# Sheet1.net
KiCad netlist of a schematic drawn in Altium Designer
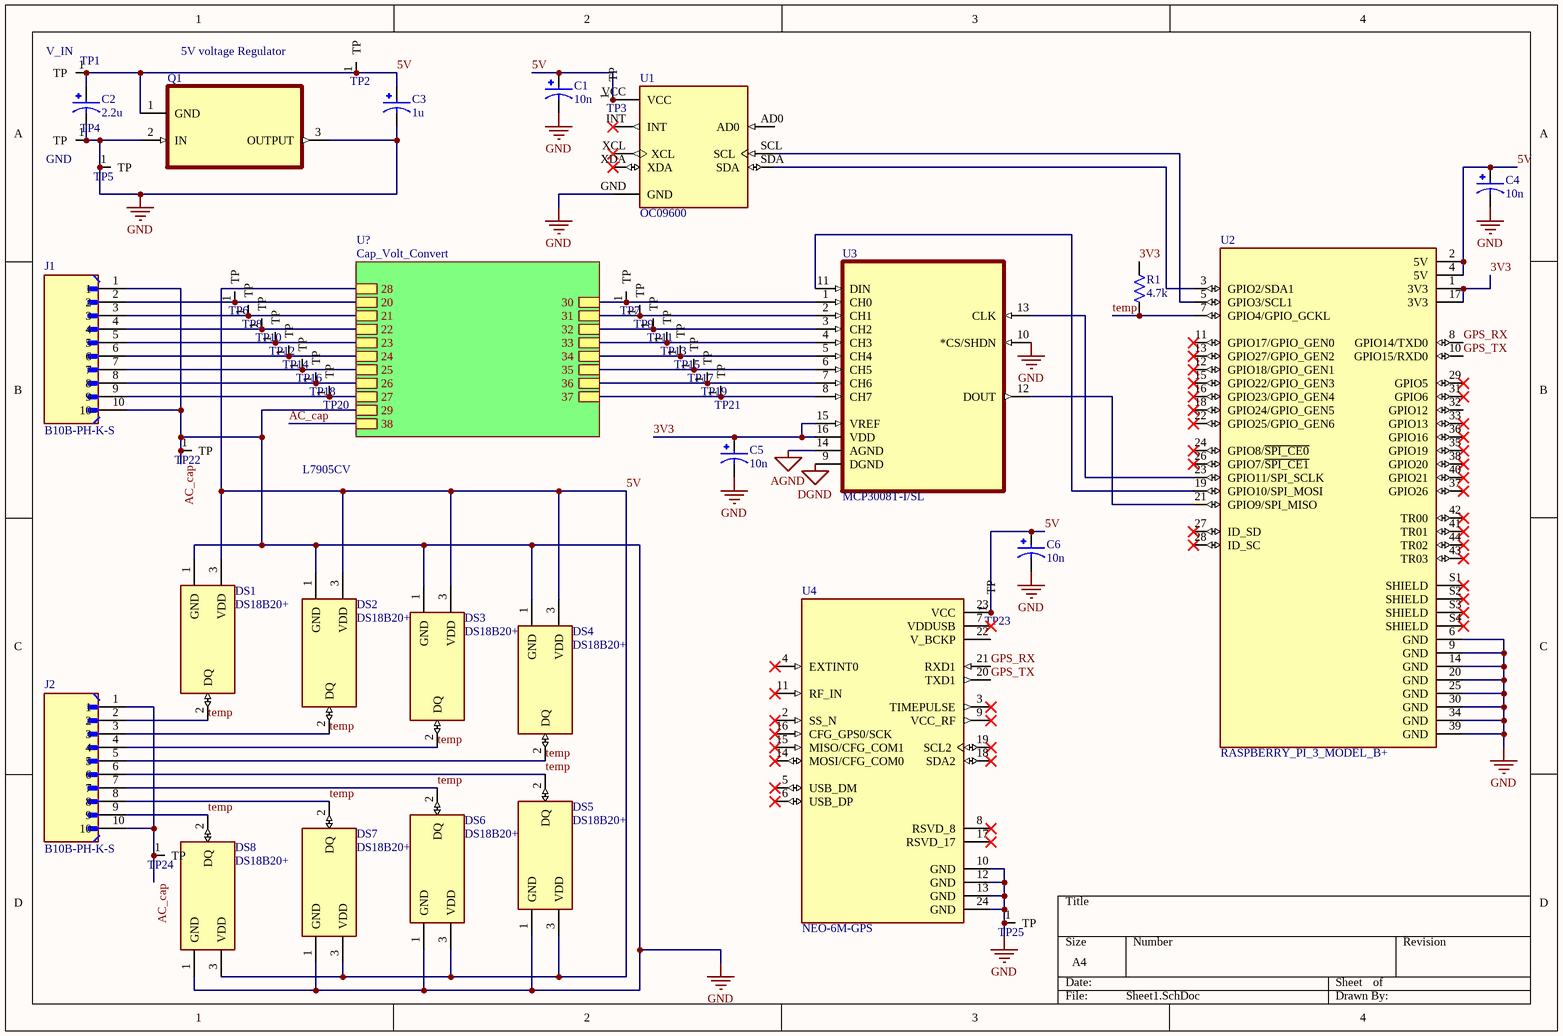
[diagram p0: Sheet1.SchDoc]

(export (version "E")
  (design (tool "Eeschema 10.0.6"))
  (components
    (comp (ref "C1")
      (value "10n")
      (footprint "CAPPRD750W80D1600H2000")
      (description "CAP ALUM 680UF 20% 63V THRU HOLE")
      (fields (field (name "MP") "EEU-FS1J681S") (field (name "MF") "Panasonic Electronic Components"))
      (libsource (lib "Schlib1") (part "EEUFS1J681S"))
    )
    (comp (ref "C2")
      (value "2.2u")
      (footprint "CAPPRD750W80D1600H2000")
      (description "CAP ALUM 680UF 20% 63V THRU HOLE")
      (fields (field (name "MP") "EEU-FS1J681S") (field (name "MF") "Panasonic Electronic Components"))
      (libsource (lib "Schlib1") (part "EEUFS1J681S"))
    )
    (comp (ref "C3")
      (value "1u")
      (footprint "CAPPRD750W80D1600H2000")
      (description "CAP ALUM 680UF 20% 63V THRU HOLE")
      (fields (field (name "MP") "EEU-FS1J681S") (field (name "MF") "Panasonic Electronic Components"))
      (libsource (lib "Schlib1") (part "EEUFS1J681S"))
    )
    (comp (ref "C4")
      (value "10n")
      (footprint "CAPPRD750W80D1600H2000")
      (description "CAP ALUM 680UF 20% 63V THRU HOLE")
      (fields (field (name "MP") "EEU-FS1J681S") (field (name "MF") "Panasonic Electronic Components"))
      (libsource (lib "Schlib1") (part "EEUFS1J681S"))
    )
    (comp (ref "C5")
      (value "10n")
      (footprint "CAPPRD750W80D1600H2000")
      (description "CAP ALUM 680UF 20% 63V THRU HOLE")
      (fields (field (name "MP") "EEU-FS1J681S") (field (name "MF") "Panasonic Electronic Components"))
      (libsource (lib "Schlib1") (part "EEUFS1J681S"))
    )
    (comp (ref "C6")
      (value "10n")
      (footprint "CAPPRD750W80D1600H2000")
      (description "CAP ALUM 680UF 20% 63V THRU HOLE")
      (fields (field (name "MP") "EEU-FS1J681S") (field (name "MF") "Panasonic Electronic Components"))
      (libsource (lib "Schlib1") (part "EEUFS1J681S"))
    )
    (comp (ref "DS1")
      (value "DS18B20+")
      (footprint "IC_DS18B20+")
      (description "Programmable Resolution 1-Wire Digital Thermometer")
      (fields (field (name "MF") "Analog Devices"))
      (libsource (lib "") (part "DS18B20+_1"))
    )
    (comp (ref "DS2")
      (value "DS18B20+")
      (footprint "IC_DS18B20+")
      (description "Programmable Resolution 1-Wire Digital Thermometer")
      (fields (field (name "MF") "Analog Devices"))
      (libsource (lib "") (part "DS18B20+_1"))
    )
    (comp (ref "DS3")
      (value "DS18B20+")
      (footprint "IC_DS18B20+")
      (description "Programmable Resolution 1-Wire Digital Thermometer")
      (fields (field (name "MF") "Analog Devices"))
      (libsource (lib "") (part "DS18B20+_1"))
    )
    (comp (ref "DS4")
      (value "DS18B20+")
      (footprint "IC_DS18B20+")
      (description "Programmable Resolution 1-Wire Digital Thermometer")
      (fields (field (name "MF") "Analog Devices"))
      (libsource (lib "") (part "DS18B20+_1"))
    )
    (comp (ref "DS5")
      (value "DS18B20+")
      (footprint "IC_DS18B20+")
      (description "Programmable Resolution 1-Wire Digital Thermometer")
      (fields (field (name "MF") "Analog Devices"))
      (libsource (lib "Schlib1") (part "DS18B20+"))
    )
    (comp (ref "DS6")
      (value "DS18B20+")
      (footprint "IC_DS18B20+")
      (description "Programmable Resolution 1-Wire Digital Thermometer")
      (fields (field (name "MF") "Analog Devices"))
      (libsource (lib "Schlib1") (part "DS18B20+"))
    )
    (comp (ref "DS7")
      (value "DS18B20+")
      (footprint "IC_DS18B20+")
      (description "Programmable Resolution 1-Wire Digital Thermometer")
      (fields (field (name "MF") "Analog Devices"))
      (libsource (lib "Schlib1") (part "DS18B20+"))
    )
    (comp (ref "DS8")
      (value "DS18B20+")
      (footprint "IC_DS18B20+")
      (description "Programmable Resolution 1-Wire Digital Thermometer")
      (fields (field (name "MF") "Analog Devices"))
      (libsource (lib "Schlib1") (part "DS18B20+"))
    )
    (comp (ref "J1")
      (value "B10B-PH-K-S")
      (footprint "JST_B10B-PH-K-S")
      (description "2.0 mm pitch/Disconnectable Crimp style connectors")
      (fields (field (name "MF") "JST Sales America Inc."))
      (libsource (lib "Schlib1") (part "B10B-PH-K-S"))
    )
    (comp (ref "J2")
      (value "B10B-PH-K-S")
      (footprint "JST_B10B-PH-K-S")
      (description "2.0 mm pitch/Disconnectable Crimp style connectors")
      (fields (field (name "MF") "JST Sales America Inc."))
      (libsource (lib "Schlib1") (part "B10B-PH-K-S"))
    )
    (comp (ref "Q1")
      (value "L7905CV")
      (footprint "TO254P450X1020X1935-3P")
      (description "Linear Voltage Regulator IC Negative Fixed 1 Output 1.5A TO-220")
      (fields (field (name "MF") "STMicroelectronics"))
      (libsource (lib "Schlib1") (part "L7905CV"))
    )
    (comp (ref "R1")
      (value "4.7k")
      (footprint "RESAD730W45L370D210")
      (description "Metal Film Resistors - Through Hole")
      (fields (field (name "MF") "YAGEO") (field (name "MP") "MFR-12FTE52-12K5"))
      (libsource (lib "Schlib1") (part "MFR-12FTE52-12K5"))
    )
    (comp (ref "TP1") (value "V_IN") (footprint "Testpoint") (libsource (lib "Schlib1") (part "Testpoint")))
    (comp (ref "TP2")
      (value "Testpoint")
      (footprint "Testpoint SMD")
      (libsource (lib "Schlib1") (part "Testpoint"))
    )
    (comp (ref "TP3")
      (value "Testpoint")
      (footprint "Testpoint SMD")
      (libsource (lib "Schlib1") (part "Testpoint"))
    )
    (comp (ref "TP4") (value "GND") (footprint "Testpoint") (libsource (lib "Schlib1") (part "Testpoint")))
    (comp (ref "TP5")
      (value "Testpoint")
      (footprint "Testpoint SMD")
      (libsource (lib "Schlib1") (part "Testpoint"))
    )
    (comp (ref "TP6")
      (value "Testpoint")
      (footprint "Testpoint SMD")
      (libsource (lib "Schlib1") (part "Testpoint"))
    )
    (comp (ref "TP7")
      (value "Testpoint")
      (footprint "Testpoint SMD")
      (libsource (lib "Schlib1") (part "Testpoint"))
    )
    (comp (ref "TP8")
      (value "Testpoint")
      (footprint "Testpoint SMD")
      (libsource (lib "Schlib1") (part "Testpoint"))
    )
    (comp (ref "TP9")
      (value "Testpoint")
      (footprint "Testpoint SMD")
      (libsource (lib "Schlib1") (part "Testpoint"))
    )
    (comp (ref "TP10")
      (value "Testpoint")
      (footprint "Testpoint SMD")
      (libsource (lib "Schlib1") (part "Testpoint"))
    )
    (comp (ref "TP11")
      (value "Testpoint")
      (footprint "Testpoint SMD")
      (libsource (lib "Schlib1") (part "Testpoint"))
    )
    (comp (ref "TP12")
      (value "Testpoint")
      (footprint "Testpoint SMD")
      (libsource (lib "Schlib1") (part "Testpoint"))
    )
    (comp (ref "TP13")
      (value "Testpoint")
      (footprint "Testpoint SMD")
      (libsource (lib "Schlib1") (part "Testpoint"))
    )
    (comp (ref "TP14")
      (value "Testpoint")
      (footprint "Testpoint SMD")
      (libsource (lib "Schlib1") (part "Testpoint"))
    )
    (comp (ref "TP15")
      (value "Testpoint")
      (footprint "Testpoint SMD")
      (libsource (lib "Schlib1") (part "Testpoint"))
    )
    (comp (ref "TP16")
      (value "Testpoint")
      (footprint "Testpoint SMD")
      (libsource (lib "Schlib1") (part "Testpoint"))
    )
    (comp (ref "TP17")
      (value "Testpoint")
      (footprint "Testpoint SMD")
      (libsource (lib "Schlib1") (part "Testpoint"))
    )
    (comp (ref "TP18")
      (value "Testpoint")
      (footprint "Testpoint SMD")
      (libsource (lib "Schlib1") (part "Testpoint"))
    )
    (comp (ref "TP19")
      (value "Testpoint")
      (footprint "Testpoint SMD")
      (libsource (lib "Schlib1") (part "Testpoint"))
    )
    (comp (ref "TP20")
      (value "Testpoint")
      (footprint "Testpoint SMD")
      (libsource (lib "Schlib1") (part "Testpoint"))
    )
    (comp (ref "TP21")
      (value "Testpoint")
      (footprint "Testpoint SMD")
      (libsource (lib "Schlib1") (part "Testpoint"))
    )
    (comp (ref "TP22")
      (value "Testpoint")
      (footprint "Testpoint")
      (libsource (lib "Schlib1") (part "Testpoint"))
    )
    (comp (ref "TP23")
      (value "Testpoint")
      (footprint "Testpoint SMD")
      (libsource (lib "Schlib1") (part "Testpoint"))
    )
    (comp (ref "TP24")
      (value "Testpoint")
      (footprint "Testpoint SMD")
      (libsource (lib "Schlib1") (part "Testpoint"))
    )
    (comp (ref "TP25")
      (value "Testpoint")
      (footprint "Testpoint SMD")
      (libsource (lib "Schlib1") (part "Testpoint"))
    )
    (comp (ref "U1")
      (value "OC09600")
      (footprint "MODULE_OC09600")
      (description "GY-521 6 DOF MPU-6050 Module 3 Axis Accelerometer Gyroscope Module for Arduino")
      (fields (field (name "MF") "YKS"))
      (libsource (lib "Schlib1") (part "OC09600"))
    )
    (comp (ref "U2")
      (value "RASPBERRY_PI_3_MODEL_B+")
      (footprint "MODULE_RASPBERRY_PI_3_MODEL_B+")
      (fields (field (name "MF") "Raspberry Pi") (field (name "MP") "RASPBERRY PI 3 MODEL B+"))
      (libsource (lib "Schlib1") (part "RASPBERRY_PI_3_MODEL_B+"))
    )
    (comp (ref "U3")
      (value "MCP3008T-I/SL")
      (footprint "SOIC127P600X175-16N")
      (description "10-bit ADC, SPI, 8-channel16 SOIC .150in T/R ¦ Microchip Technology Inc. MCP3008T-I/SL")
      (fields (field (name "MF") "Microchip Technology"))
      (libsource (lib "Schlib1") (part "MCP3008T-I/SL"))
    )
    (comp (ref "U4")
      (value "NEO-6M-GPS")
      (footprint "XCVR_NEO-6M-GPS")
      (description "GPS Development Tools SparkFun GNSS-RTK Dead Reckoning Breakout - ZED-F9K (Qwiic)")
      (fields (field (name "MF") "u-blox"))
      (libsource (lib "Schlib1") (part "NEO-6M-GPS"))
    )
  )
  (nets
    (net (code "1") (name "/3V3") (class "Default")
      (node (ref "C5") (pin "P") (pinfunction "P_P") (pintype "passive"))
      (node (ref "R1") (pin "2") (pinfunction "2_2") (pintype "passive"))
      (node (ref "U2") (pin "1") (pinfunction "3V3_1") (pintype "power_in"))
      (node (ref "U2") (pin "17") (pinfunction "3V3_17") (pintype "power_in"))
      (node (ref "U3") (pin "15") (pinfunction "VREF_15") (pintype "input"))
      (node (ref "U3") (pin "16") (pinfunction "VDD_16") (pintype "power_in"))
    )
    (net (code "2") (name "/5V") (class "Default")
      (node (ref "C1") (pin "P") (pinfunction "P_P") (pintype "passive"))
      (node (ref "C2") (pin "P") (pinfunction "P_P") (pintype "passive"))
      (node (ref "C3") (pin "P") (pinfunction "P_P") (pintype "passive"))
      (node (ref "C4") (pin "P") (pinfunction "P_P") (pintype "passive"))
      (node (ref "C6") (pin "P") (pinfunction "P_P") (pintype "passive"))
      (node (ref "DS1") (pin "3") (pinfunction "VDD_3") (pintype "power_in"))
      (node (ref "DS2") (pin "3") (pinfunction "VDD_3") (pintype "power_in"))
      (node (ref "DS3") (pin "3") (pinfunction "VDD_3") (pintype "power_in"))
      (node (ref "DS4") (pin "3") (pinfunction "VDD_3") (pintype "power_in"))
      (node (ref "DS5") (pin "3") (pinfunction "VDD_3") (pintype "power_in"))
      (node (ref "DS6") (pin "3") (pinfunction "VDD_3") (pintype "power_in"))
      (node (ref "DS7") (pin "3") (pinfunction "VDD_3") (pintype "power_in"))
      (node (ref "DS8") (pin "3") (pinfunction "VDD_3") (pintype "power_in"))
      (node (ref "Q1") (pin "1") (pinfunction "GND_1") (pintype "passive"))
      (node (ref "TP1") (pin "1") (pinfunction "TP_1") (pintype "passive"))
      (node (ref "TP2") (pin "1") (pinfunction "TP_1") (pintype "passive"))
      (node (ref "TP23") (pin "1") (pinfunction "TP_1") (pintype "passive"))
      (node (ref "TP3") (pin "1") (pinfunction "TP_1") (pintype "passive"))
      (node (ref "U1") (pin "VCC") (pinfunction "VCC_VCC") (pintype "power_in"))
      (node (ref "U2") (pin "2") (pinfunction "5V_2") (pintype "power_in"))
      (node (ref "U2") (pin "4") (pinfunction "5V_4") (pintype "power_in"))
      (node (ref "U4") (pin "23") (pinfunction "VCC_23") (pintype "power_in"))
    )
    (net (code "3") (name "/20") (class "Default")
      (node (ref "J1") (pin "2") (pinfunction "2_2") (pintype "passive"))
      (node (ref "TP6") (pin "1") (pinfunction "TP_1") (pintype "passive"))
    )
    (net (code "4") (name "/21") (class "Default")
      (node (ref "J1") (pin "3") (pinfunction "3_3") (pintype "passive"))
      (node (ref "TP8") (pin "1") (pinfunction "TP_1") (pintype "passive"))
    )
    (net (code "5") (name "/22") (class "Default")
      (node (ref "J1") (pin "4") (pinfunction "4_4") (pintype "passive"))
      (node (ref "TP10") (pin "1") (pinfunction "TP_1") (pintype "passive"))
    )
    (net (code "6") (name "/23") (class "Default")
      (node (ref "J1") (pin "5") (pinfunction "5_5") (pintype "passive"))
      (node (ref "TP12") (pin "1") (pinfunction "TP_1") (pintype "passive"))
    )
    (net (code "7") (name "/24") (class "Default")
      (node (ref "J1") (pin "6") (pinfunction "6_6") (pintype "passive"))
      (node (ref "TP14") (pin "1") (pinfunction "TP_1") (pintype "passive"))
    )
    (net (code "8") (name "/25") (class "Default")
      (node (ref "J1") (pin "7") (pinfunction "7_7") (pintype "passive"))
      (node (ref "TP16") (pin "1") (pinfunction "TP_1") (pintype "passive"))
    )
    (net (code "9") (name "/26") (class "Default")
      (node (ref "J1") (pin "8") (pinfunction "8_8") (pintype "passive"))
      (node (ref "TP18") (pin "1") (pinfunction "TP_1") (pintype "passive"))
    )
    (net (code "10") (name "/27") (class "Default")
      (node (ref "J1") (pin "9") (pinfunction "9_9") (pintype "passive"))
      (node (ref "TP20") (pin "1") (pinfunction "TP_1") (pintype "passive"))
    )
    (net (code "11") (name "/30") (class "Default")
      (node (ref "TP7") (pin "1") (pinfunction "TP_1") (pintype "passive"))
      (node (ref "U3") (pin "1") (pinfunction "CH0_1") (pintype "input"))
    )
    (net (code "12") (name "/31") (class "Default")
      (node (ref "TP9") (pin "1") (pinfunction "TP_1") (pintype "passive"))
      (node (ref "U3") (pin "2") (pinfunction "CH1_2") (pintype "input"))
    )
    (net (code "13") (name "/32") (class "Default")
      (node (ref "TP11") (pin "1") (pinfunction "TP_1") (pintype "passive"))
      (node (ref "U3") (pin "3") (pinfunction "CH2_3") (pintype "input"))
    )
    (net (code "14") (name "/33") (class "Default")
      (node (ref "TP13") (pin "1") (pinfunction "TP_1") (pintype "passive"))
      (node (ref "U3") (pin "4") (pinfunction "CH3_4") (pintype "input"))
    )
    (net (code "15") (name "/34") (class "Default")
      (node (ref "TP15") (pin "1") (pinfunction "TP_1") (pintype "passive"))
      (node (ref "U3") (pin "5") (pinfunction "CH4_5") (pintype "input"))
    )
    (net (code "16") (name "/35") (class "Default")
      (node (ref "TP17") (pin "1") (pinfunction "TP_1") (pintype "passive"))
      (node (ref "U3") (pin "6") (pinfunction "CH5_6") (pintype "input"))
    )
    (net (code "17") (name "/36") (class "Default")
      (node (ref "TP19") (pin "1") (pinfunction "TP_1") (pintype "passive"))
      (node (ref "U3") (pin "7") (pinfunction "CH6_7") (pintype "input"))
    )
    (net (code "18") (name "/37") (class "Default")
      (node (ref "TP21") (pin "1") (pinfunction "TP_1") (pintype "passive"))
      (node (ref "U3") (pin "8") (pinfunction "CH7_8") (pintype "input"))
    )
    (net (code "19") (name "/GPS_RX") (class "Default")
      (node (ref "U2") (pin "8") (pinfunction "GPIO14/TXD0_8") (pintype "bidirectional"))
      (node (ref "U4") (pin "21") (pinfunction "RXD1_21") (pintype "input"))
    )
    (net (code "20") (name "/GPS_TX") (class "Default")
      (node (ref "U2") (pin "10") (pinfunction "GPIO15/RXD0_10") (pintype "bidirectional"))
      (node (ref "U4") (pin "20") (pinfunction "TXD1_20") (pintype "output"))
    )
    (net (code "21") (name "/temp") (class "Default")
      (node (ref "DS1") (pin "2") (pinfunction "DQ_2") (pintype "bidirectional"))
      (node (ref "DS2") (pin "2") (pinfunction "DQ_2") (pintype "bidirectional"))
      (node (ref "DS3") (pin "2") (pinfunction "DQ_2") (pintype "bidirectional"))
      (node (ref "DS4") (pin "2") (pinfunction "DQ_2") (pintype "bidirectional"))
      (node (ref "DS5") (pin "2") (pinfunction "DQ_2") (pintype "bidirectional"))
      (node (ref "DS6") (pin "2") (pinfunction "DQ_2") (pintype "bidirectional"))
      (node (ref "DS7") (pin "2") (pinfunction "DQ_2") (pintype "bidirectional"))
      (node (ref "DS8") (pin "2") (pinfunction "DQ_2") (pintype "bidirectional"))
      (node (ref "J2") (pin "2") (pinfunction "2_2") (pintype "passive"))
      (node (ref "J2") (pin "3") (pinfunction "3_3") (pintype "passive"))
      (node (ref "J2") (pin "4") (pinfunction "4_4") (pintype "passive"))
      (node (ref "J2") (pin "5") (pinfunction "5_5") (pintype "passive"))
      (node (ref "J2") (pin "6") (pinfunction "6_6") (pintype "passive"))
      (node (ref "J2") (pin "7") (pinfunction "7_7") (pintype "passive"))
      (node (ref "J2") (pin "8") (pinfunction "8_8") (pintype "passive"))
      (node (ref "J2") (pin "9") (pinfunction "9_9") (pintype "passive"))
      (node (ref "R1") (pin "1") (pinfunction "1_1") (pintype "passive"))
      (node (ref "U2") (pin "7") (pinfunction "GPIO4/GPIO_GCKL_7") (pintype "bidirectional"))
    )
    (net (code "22") (name "AGND") (class "Default")
      (node (ref "U3") (pin "14") (pinfunction "AGND_14") (pintype "passive"))
    )
    (net (code "23") (name "DGND") (class "Default")
      (node (ref "U3") (pin "9") (pinfunction "DGND_9") (pintype "passive"))
    )
    (net (code "24") (name "GND") (class "Default")
      (node (ref "C1") (pin "N") (pinfunction "N_N") (pintype "passive"))
      (node (ref "C2") (pin "N") (pinfunction "N_N") (pintype "passive"))
      (node (ref "C3") (pin "N") (pinfunction "N_N") (pintype "passive"))
      (node (ref "C4") (pin "N") (pinfunction "N_N") (pintype "passive"))
      (node (ref "C5") (pin "N") (pinfunction "N_N") (pintype "passive"))
      (node (ref "C6") (pin "N") (pinfunction "N_N") (pintype "passive"))
      (node (ref "DS1") (pin "1") (pinfunction "GND_1") (pintype "power_in"))
      (node (ref "DS2") (pin "1") (pinfunction "GND_1") (pintype "power_in"))
      (node (ref "DS3") (pin "1") (pinfunction "GND_1") (pintype "power_in"))
      (node (ref "DS4") (pin "1") (pinfunction "GND_1") (pintype "power_in"))
      (node (ref "DS5") (pin "1") (pinfunction "GND_1") (pintype "power_in"))
      (node (ref "DS6") (pin "1") (pinfunction "GND_1") (pintype "power_in"))
      (node (ref "DS7") (pin "1") (pinfunction "GND_1") (pintype "power_in"))
      (node (ref "DS8") (pin "1") (pinfunction "GND_1") (pintype "power_in"))
      (node (ref "J1") (pin "1") (pinfunction "1_1") (pintype "passive"))
      (node (ref "J1") (pin "10") (pinfunction "10_10") (pintype "passive"))
      (node (ref "J2") (pin "1") (pinfunction "1_1") (pintype "passive"))
      (node (ref "J2") (pin "10") (pinfunction "10_10") (pintype "passive"))
      (node (ref "Q1") (pin "2") (pinfunction "IN_2") (pintype "input"))
      (node (ref "Q1") (pin "3") (pinfunction "OUTPUT_3") (pintype "output"))
      (node (ref "TP22") (pin "1") (pinfunction "TP_1") (pintype "passive"))
      (node (ref "TP24") (pin "1") (pinfunction "TP_1") (pintype "passive"))
      (node (ref "TP25") (pin "1") (pinfunction "TP_1") (pintype "passive"))
      (node (ref "TP4") (pin "1") (pinfunction "TP_1") (pintype "passive"))
      (node (ref "TP5") (pin "1") (pinfunction "TP_1") (pintype "passive"))
      (node (ref "U1") (pin "GND") (pinfunction "GND_GND") (pintype "power_in"))
      (node (ref "U2") (pin "14") (pinfunction "GND_14") (pintype "power_in"))
      (node (ref "U2") (pin "20") (pinfunction "GND_20") (pintype "power_in"))
      (node (ref "U2") (pin "25") (pinfunction "GND_25") (pintype "power_in"))
      (node (ref "U2") (pin "30") (pinfunction "GND_30") (pintype "power_in"))
      (node (ref "U2") (pin "34") (pinfunction "GND_34") (pintype "power_in"))
      (node (ref "U2") (pin "39") (pinfunction "GND_39") (pintype "power_in"))
      (node (ref "U2") (pin "6") (pinfunction "GND_6") (pintype "power_in"))
      (node (ref "U2") (pin "9") (pinfunction "GND_9") (pintype "power_in"))
      (node (ref "U3") (pin "10") (pinfunction "*CS/SHDN_10") (pintype "input"))
      (node (ref "U4") (pin "10") (pinfunction "GND_10") (pintype "power_in"))
      (node (ref "U4") (pin "12") (pinfunction "GND_12") (pintype "power_in"))
      (node (ref "U4") (pin "13") (pinfunction "GND_13") (pintype "power_in"))
      (node (ref "U4") (pin "24") (pinfunction "GND_24") (pintype "power_in"))
    )
    (net (code "25") (name "Net-(U2-GPIO2{slash}SDA1)") (class "Default")
      (node (ref "U1") (pin "SDA") (pinfunction "SDA_SDA") (pintype "bidirectional"))
      (node (ref "U2") (pin "3") (pinfunction "GPIO2/SDA1_3") (pintype "bidirectional"))
    )
    (net (code "26") (name "Net-(U2-GPIO3{slash}SCL1)") (class "Default")
      (node (ref "U1") (pin "SCL") (pinfunction "SCL_SCL") (pintype "input"))
      (node (ref "U2") (pin "5") (pinfunction "GPIO3/SCL1_5") (pintype "bidirectional"))
    )
    (net (code "27") (name "Net-(U2-GPIO9{slash}SPI_MISO)") (class "Default")
      (node (ref "U2") (pin "21") (pinfunction "GPIO9/SPI_MISO_21") (pintype "bidirectional"))
      (node (ref "U3") (pin "12") (pinfunction "DOUT_12") (pintype "output"))
    )
    (net (code "28") (name "Net-(U2-GPIO10{slash}SPI_MOSI)") (class "Default")
      (node (ref "U2") (pin "19") (pinfunction "GPIO10/SPI_MOSI_19") (pintype "bidirectional"))
      (node (ref "U3") (pin "11") (pinfunction "DIN_11") (pintype "input"))
    )
    (net (code "29") (name "Net-(U2-GPIO11{slash}SPI_SCLK)") (class "Default")
      (node (ref "U2") (pin "23") (pinfunction "GPIO11/SPI_SCLK_23") (pintype "bidirectional"))
      (node (ref "U3") (pin "13") (pinfunction "CLK_13") (pintype "input"))
    )
    (net (code "30") (name "unconnected-(U1-PadAD0)") (class "Default")
      (node (ref "U1") (pin "AD0") (pinfunction "AD0_AD0") (pintype "input"))
    )
    (net (code "31") (name "unconnected-(U1-PadINT)") (class "Default")
      (node (ref "U1") (pin "INT") (pinfunction "INT_INT") (pintype "output+no_connect"))
    )
    (net (code "32") (name "unconnected-(U1-PadXCL)") (class "Default")
      (node (ref "U1") (pin "XCL") (pinfunction "XCL_XCL") (pintype "output+no_connect"))
    )
    (net (code "33") (name "unconnected-(U1-PadXDA)") (class "Default")
      (node (ref "U1") (pin "XDA") (pinfunction "XDA_XDA") (pintype "bidirectional+no_connect"))
    )
    (net (code "34") (name "unconnected-(U2-GPIO5-Pad29)") (class "Default")
      (node (ref "U2") (pin "29") (pinfunction "GPIO5_29") (pintype "bidirectional+no_connect"))
    )
    (net (code "35") (name "unconnected-(U2-GPIO6-Pad31)") (class "Default")
      (node (ref "U2") (pin "31") (pinfunction "GPIO6_31") (pintype "bidirectional+no_connect"))
    )
    (net (code "36") (name "unconnected-(U2-GPIO7{slash}~{SPI_CE1}-Pad26)") (class "Default")
      (node (ref "U2") (pin "26") (pinfunction "GPIO7/~{SPI_CE1}_26") (pintype "bidirectional+no_connect"))
    )
    (net (code "37") (name "unconnected-(U2-GPIO8{slash}~{SPI_CE0}-Pad24)") (class "Default")
      (node (ref "U2") (pin "24") (pinfunction "GPIO8/~{SPI_CE0}_24") (pintype "bidirectional+no_connect"))
    )
    (net (code "38") (name "unconnected-(U2-GPIO12-Pad32)") (class "Default")
      (node (ref "U2") (pin "32") (pinfunction "GPIO12_32") (pintype "bidirectional"))
    )
    (net (code "39") (name "unconnected-(U2-GPIO13-Pad33)") (class "Default")
      (node (ref "U2") (pin "33") (pinfunction "GPIO13_33") (pintype "bidirectional+no_connect"))
    )
    (net (code "40") (name "unconnected-(U2-GPIO16-Pad36)") (class "Default")
      (node (ref "U2") (pin "36") (pinfunction "GPIO16_36") (pintype "bidirectional+no_connect"))
    )
    (net (code "41") (name "unconnected-(U2-GPIO17{slash}GPIO_GEN0-Pad11)") (class "Default")
      (node (ref "U2") (pin "11") (pinfunction "GPIO17/GPIO_GEN0_11") (pintype "bidirectional+no_connect"))
    )
    (net (code "42") (name "unconnected-(U2-GPIO18{slash}GPIO_GEN1-Pad12)") (class "Default")
      (node (ref "U2") (pin "12") (pinfunction "GPIO18/GPIO_GEN1_12") (pintype "bidirectional+no_connect"))
    )
    (net (code "43") (name "unconnected-(U2-GPIO19-Pad35)") (class "Default")
      (node (ref "U2") (pin "35") (pinfunction "GPIO19_35") (pintype "bidirectional+no_connect"))
    )
    (net (code "44") (name "unconnected-(U2-GPIO20-Pad38)") (class "Default")
      (node (ref "U2") (pin "38") (pinfunction "GPIO20_38") (pintype "bidirectional+no_connect"))
    )
    (net (code "45") (name "unconnected-(U2-GPIO21-Pad40)") (class "Default")
      (node (ref "U2") (pin "40") (pinfunction "GPIO21_40") (pintype "bidirectional+no_connect"))
    )
    (net (code "46") (name "unconnected-(U2-GPIO22{slash}GPIO_GEN3-Pad15)") (class "Default")
      (node (ref "U2") (pin "15") (pinfunction "GPIO22/GPIO_GEN3_15") (pintype "bidirectional+no_connect"))
    )
    (net (code "47") (name "unconnected-(U2-GPIO23{slash}GPIO_GEN4-Pad16)") (class "Default")
      (node (ref "U2") (pin "16") (pinfunction "GPIO23/GPIO_GEN4_16") (pintype "bidirectional+no_connect"))
    )
    (net (code "48") (name "unconnected-(U2-GPIO24{slash}GPIO_GEN5-Pad18)") (class "Default")
      (node (ref "U2") (pin "18") (pinfunction "GPIO24/GPIO_GEN5_18") (pintype "bidirectional+no_connect"))
    )
    (net (code "49") (name "unconnected-(U2-GPIO25{slash}GPIO_GEN6-Pad22)") (class "Default")
      (node (ref "U2") (pin "22") (pinfunction "GPIO25/GPIO_GEN6_22") (pintype "bidirectional+no_connect"))
    )
    (net (code "50") (name "unconnected-(U2-GPIO26-Pad37)") (class "Default")
      (node (ref "U2") (pin "37") (pinfunction "GPIO26_37") (pintype "bidirectional+no_connect"))
    )
    (net (code "51") (name "unconnected-(U2-GPIO27{slash}GPIO_GEN2-Pad13)") (class "Default")
      (node (ref "U2") (pin "13") (pinfunction "GPIO27/GPIO_GEN2_13") (pintype "bidirectional+no_connect"))
    )
    (net (code "52") (name "unconnected-(U2-ID_SC-Pad28)") (class "Default")
      (node (ref "U2") (pin "28") (pinfunction "ID_SC_28") (pintype "bidirectional+no_connect"))
    )
    (net (code "53") (name "unconnected-(U2-ID_SD-Pad27)") (class "Default")
      (node (ref "U2") (pin "27") (pinfunction "ID_SD_27") (pintype "bidirectional+no_connect"))
    )
    (net (code "54") (name "unconnected-(U2-SHIELD-PadS1)") (class "Default")
      (node (ref "U2") (pin "S1") (pinfunction "SHIELD_S1") (pintype "power_in+no_connect"))
    )
    (net (code "55") (name "unconnected-(U2-SHIELD-PadS2)") (class "Default")
      (node (ref "U2") (pin "S2") (pinfunction "SHIELD_S2") (pintype "power_in+no_connect"))
    )
    (net (code "56") (name "unconnected-(U2-SHIELD-PadS3)") (class "Default")
      (node (ref "U2") (pin "S3") (pinfunction "SHIELD_S3") (pintype "power_in+no_connect"))
    )
    (net (code "57") (name "unconnected-(U2-SHIELD-PadS4)") (class "Default")
      (node (ref "U2") (pin "S4") (pinfunction "SHIELD_S4") (pintype "power_in+no_connect"))
    )
    (net (code "58") (name "unconnected-(U2-TR00-Pad42)") (class "Default")
      (node (ref "U2") (pin "42") (pinfunction "TR00_42") (pintype "bidirectional+no_connect"))
    )
    (net (code "59") (name "unconnected-(U2-TR01-Pad41)") (class "Default")
      (node (ref "U2") (pin "41") (pinfunction "TR01_41") (pintype "bidirectional+no_connect"))
    )
    (net (code "60") (name "unconnected-(U2-TR02-Pad44)") (class "Default")
      (node (ref "U2") (pin "44") (pinfunction "TR02_44") (pintype "bidirectional+no_connect"))
    )
    (net (code "61") (name "unconnected-(U2-TR03-Pad43)") (class "Default")
      (node (ref "U2") (pin "43") (pinfunction "TR03_43") (pintype "bidirectional+no_connect"))
    )
    (net (code "62") (name "unconnected-(U4-CFG_GPS0{slash}SCK-Pad16)") (class "Default")
      (node (ref "U4") (pin "16") (pinfunction "CFG_GPS0/SCK_16") (pintype "input+no_connect"))
    )
    (net (code "63") (name "unconnected-(U4-EXTINT0-Pad4)") (class "Default")
      (node (ref "U4") (pin "4") (pinfunction "EXTINT0_4") (pintype "input+no_connect"))
    )
    (net (code "64") (name "unconnected-(U4-MISO{slash}CFG_COM1-Pad15)") (class "Default")
      (node (ref "U4") (pin "15") (pinfunction "MISO/CFG_COM1_15") (pintype "input+no_connect"))
    )
    (net (code "65") (name "unconnected-(U4-MOSI{slash}CFG_COM0-Pad14)") (class "Default")
      (node (ref "U4") (pin "14") (pinfunction "MOSI/CFG_COM0_14") (pintype "bidirectional+no_connect"))
    )
    (net (code "66") (name "unconnected-(U4-RF_IN-Pad11)") (class "Default")
      (node (ref "U4") (pin "11") (pinfunction "RF_IN_11") (pintype "input+no_connect"))
    )
    (net (code "67") (name "unconnected-(U4-RSVD_8-Pad8)") (class "Default")
      (node (ref "U4") (pin "8") (pinfunction "RSVD_8_8") (pintype "passive+no_connect"))
    )
    (net (code "68") (name "unconnected-(U4-RSVD_17-Pad17)") (class "Default")
      (node (ref "U4") (pin "17") (pinfunction "RSVD_17_17") (pintype "passive+no_connect"))
    )
    (net (code "69") (name "unconnected-(U4-SCL2-Pad19)") (class "Default")
      (node (ref "U4") (pin "19") (pinfunction "SCL2_19") (pintype "bidirectional+no_connect"))
    )
    (net (code "70") (name "unconnected-(U4-SDA2-Pad18)") (class "Default")
      (node (ref "U4") (pin "18") (pinfunction "SDA2_18") (pintype "bidirectional+no_connect"))
    )
    (net (code "71") (name "unconnected-(U4-SS_N-Pad2)") (class "Default")
      (node (ref "U4") (pin "2") (pinfunction "SS_N_2") (pintype "input+no_connect"))
    )
    (net (code "72") (name "unconnected-(U4-TIMEPULSE-Pad3)") (class "Default")
      (node (ref "U4") (pin "3") (pinfunction "TIMEPULSE_3") (pintype "output+no_connect"))
    )
    (net (code "73") (name "unconnected-(U4-USB_DM-Pad5)") (class "Default")
      (node (ref "U4") (pin "5") (pinfunction "USB_DM_5") (pintype "bidirectional+no_connect"))
    )
    (net (code "74") (name "unconnected-(U4-USB_DP-Pad6)") (class "Default")
      (node (ref "U4") (pin "6") (pinfunction "USB_DP_6") (pintype "bidirectional+no_connect"))
    )
    (net (code "75") (name "unconnected-(U4-VCC_RF-Pad9)") (class "Default")
      (node (ref "U4") (pin "9") (pinfunction "VCC_RF_9") (pintype "output+no_connect"))
    )
    (net (code "76") (name "unconnected-(U4-VDDUSB-Pad7)") (class "Default")
      (node (ref "U4") (pin "7") (pinfunction "VDDUSB_7") (pintype "power_in+no_connect"))
    )
    (net (code "77") (name "unconnected-(U4-V_BCKP-Pad22)") (class "Default")
      (node (ref "U4") (pin "22") (pinfunction "V_BCKP_22") (pintype "power_in"))
    )
  )
)
